# MIPI_FLAT_22PIN.net
KiCad netlist of a schematic drawn in Altium Designer
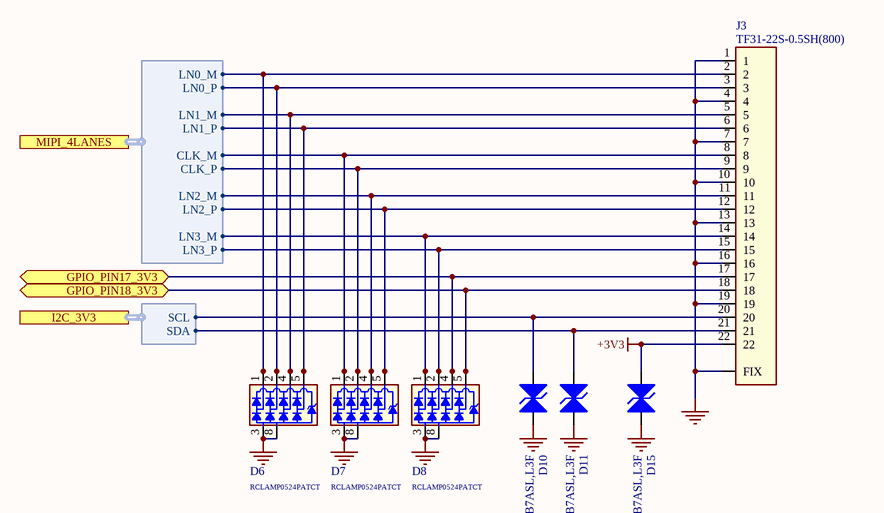
[diagram p0: MIPI_FLAT_22PIN.SchDoc]

(export (version "E")
  (design (tool "Eeschema 10.0.6"))
  (components
    (comp (ref "D6")
      (value "RCLAMP0524PATCT")
      (footprint "SLP2510P8")
      (description "TVS UNIDIRECTIONAL 4CH 0.8pF 5V SLP2510P8 10-pin 2.5x1.0x0.58mm")
      (fields (field (name "MANUFACTURER") "SEMTECH"))
      (libsource (lib "Clean") (part "RCLAMP0524PATCT"))
    )
    (comp (ref "D7")
      (value "RCLAMP0524PATCT")
      (footprint "SLP2510P8")
      (description "TVS UNIDIRECTIONAL 4CH 0.8pF 5V SLP2510P8 10-pin 2.5x1.0x0.58mm")
      (fields (field (name "MANUFACTURER") "SEMTECH"))
      (libsource (lib "Clean") (part "RCLAMP0524PATCT"))
    )
    (comp (ref "D8")
      (value "RCLAMP0524PATCT")
      (footprint "SLP2510P8")
      (description "TVS UNIDIRECTIONAL 4CH 0.8pF 5V SLP2510P8 10-pin 2.5x1.0x0.58mm")
      (fields (field (name "MANUFACTURER") "SEMTECH"))
      (libsource (lib "Clean") (part "RCLAMP0524PATCT"))
    )
    (comp (ref "D10")
      (value "DF2B7ASL,L3F")
      (footprint "DF2B7ASL,L3F")
      (description "TVS BIDIRECTIONAL SMD Vr 5.5V, Vbr min 5.8V, 0.62x0.32mm")
      (fields (field (name "MANUFACTURER") "TOSHIBA"))
      (libsource (lib "Clean") (part "Diode TVS"))
    )
    (comp (ref "D11")
      (value "DF2B7ASL,L3F")
      (footprint "DF2B7ASL,L3F")
      (description "TVS BIDIRECTIONAL SMD Vr 5.5V, Vbr min 5.8V, 0.62x0.32mm")
      (fields (field (name "MANUFACTURER") "TOSHIBA"))
      (libsource (lib "Clean") (part "Diode TVS"))
    )
    (comp (ref "D15")
      (value "DF2B7ASL,L3F")
      (footprint "DF2B7ASL,L3F")
      (description "TVS BIDIRECTIONAL SMD Vr 5.5V, Vbr min 5.8V, 0.62x0.32mm")
      (fields (field (name "MANUFACTURER") "TOSHIBA"))
      (libsource (lib "Clean") (part "Diode TVS"))
    )
    (comp (ref "J3")
      (value "TF31-22S-0.5SH(800)")
      (footprint "TF31-22S-0.5SH(800)")
      (description "CONN FFC/FPC Connector, 22 Contact(s), 1 Row(s), BOTTOM CONTACT, Female, Right Angle, 0.5mm Pitch")
      (fields (field (name "MANUFACTURER") "Hirose"))
      (libsource (lib "Clean") (part "TF31-22S-0.5SH(800)"))
    )
  )
  (nets
    (net (code "3") (name "+3V3") (class "Default")
      (node (ref "D15") (pin "2") (pinfunction "A2_2") (pintype "passive"))
      (node (ref "J3") (pin "22") (pinfunction "22_22") (pintype "passive"))
    )
    (net (code "4") (name "/GPIO_PIN17_3V3") (class "Default")
      (node (ref "D8") (pin "4") (pinfunction "4_4") (pintype "passive"))
      (node (ref "D8") (pin "7") (pinfunction "7_7") (pintype "passive"))
      (node (ref "J3") (pin "17") (pinfunction "17_17") (pintype "passive"))
    )
    (net (code "5") (name "/GPIO_PIN18_3V3") (class "Default")
      (node (ref "D8") (pin "5") (pinfunction "5_5") (pintype "passive"))
      (node (ref "D8") (pin "6") (pinfunction "6_6") (pintype "passive"))
      (node (ref "J3") (pin "18") (pinfunction "18_18") (pintype "passive"))
    )
    (net (code "8") (name "GND") (class "Default")
      (node (ref "D10") (pin "1") (pinfunction "A1_1") (pintype "passive"))
      (node (ref "D11") (pin "1") (pinfunction "A1_1") (pintype "passive"))
      (node (ref "D15") (pin "1") (pinfunction "A1_1") (pintype "passive"))
      (node (ref "D6") (pin "3") (pinfunction "3_3") (pintype "passive"))
      (node (ref "D6") (pin "8") (pinfunction "8_8") (pintype "passive"))
      (node (ref "D7") (pin "3") (pinfunction "3_3") (pintype "passive"))
      (node (ref "D7") (pin "8") (pinfunction "8_8") (pintype "passive"))
      (node (ref "D8") (pin "3") (pinfunction "3_3") (pintype "passive"))
      (node (ref "D8") (pin "8") (pinfunction "8_8") (pintype "passive"))
      (node (ref "J3") (pin "1") (pinfunction "1_1") (pintype "passive"))
      (node (ref "J3") (pin "10") (pinfunction "10_10") (pintype "passive"))
      (node (ref "J3") (pin "13") (pinfunction "13_13") (pintype "passive"))
      (node (ref "J3") (pin "16") (pinfunction "16_16") (pintype "passive"))
      (node (ref "J3") (pin "19") (pinfunction "19_19") (pintype "passive"))
      (node (ref "J3") (pin "4") (pinfunction "4_4") (pintype "passive"))
      (node (ref "J3") (pin "7") (pinfunction "7_7") (pintype "passive"))
      (node (ref "J3") (pin "FIX") (pinfunction "FIX_FIX") (pintype "passive"))
    )
    (net (code "9") (name "Net-(D6-Pad1)") (class "Default")
      (node (ref "D6") (pin "1") (pinfunction "1_1") (pintype "passive"))
      (node (ref "D6") (pin "10") (pinfunction "10_10") (pintype "passive"))
      (node (ref "J3") (pin "2") (pinfunction "2_2") (pintype "passive"))
    )
    (net (code "10") (name "Net-(D6-Pad2)") (class "Default")
      (node (ref "D6") (pin "2") (pinfunction "2_2") (pintype "passive"))
      (node (ref "D6") (pin "9") (pinfunction "9_9") (pintype "passive"))
      (node (ref "J3") (pin "3") (pinfunction "3_3") (pintype "passive"))
    )
    (net (code "11") (name "Net-(D6-Pad4)") (class "Default")
      (node (ref "D6") (pin "4") (pinfunction "4_4") (pintype "passive"))
      (node (ref "D6") (pin "7") (pinfunction "7_7") (pintype "passive"))
      (node (ref "J3") (pin "5") (pinfunction "5_5") (pintype "passive"))
    )
    (net (code "12") (name "Net-(D6-Pad5)") (class "Default")
      (node (ref "D6") (pin "5") (pinfunction "5_5") (pintype "passive"))
      (node (ref "D6") (pin "6") (pinfunction "6_6") (pintype "passive"))
      (node (ref "J3") (pin "6") (pinfunction "6_6") (pintype "passive"))
    )
    (net (code "13") (name "Net-(D7-Pad1)") (class "Default")
      (node (ref "D7") (pin "1") (pinfunction "1_1") (pintype "passive"))
      (node (ref "D7") (pin "10") (pinfunction "10_10") (pintype "passive"))
      (node (ref "J3") (pin "8") (pinfunction "8_8") (pintype "passive"))
    )
    (net (code "14") (name "Net-(D7-Pad2)") (class "Default")
      (node (ref "D7") (pin "2") (pinfunction "2_2") (pintype "passive"))
      (node (ref "D7") (pin "9") (pinfunction "9_9") (pintype "passive"))
      (node (ref "J3") (pin "9") (pinfunction "9_9") (pintype "passive"))
    )
    (net (code "15") (name "Net-(D7-Pad4)") (class "Default")
      (node (ref "D7") (pin "4") (pinfunction "4_4") (pintype "passive"))
      (node (ref "D7") (pin "7") (pinfunction "7_7") (pintype "passive"))
      (node (ref "J3") (pin "11") (pinfunction "11_11") (pintype "passive"))
    )
    (net (code "16") (name "Net-(D7-Pad5)") (class "Default")
      (node (ref "D7") (pin "5") (pinfunction "5_5") (pintype "passive"))
      (node (ref "D7") (pin "6") (pinfunction "6_6") (pintype "passive"))
      (node (ref "J3") (pin "12") (pinfunction "12_12") (pintype "passive"))
    )
    (net (code "17") (name "Net-(D8-Pad1)") (class "Default")
      (node (ref "D8") (pin "1") (pinfunction "1_1") (pintype "passive"))
      (node (ref "D8") (pin "10") (pinfunction "10_10") (pintype "passive"))
      (node (ref "J3") (pin "14") (pinfunction "14_14") (pintype "passive"))
    )
    (net (code "18") (name "Net-(D8-Pad2)") (class "Default")
      (node (ref "D8") (pin "2") (pinfunction "2_2") (pintype "passive"))
      (node (ref "D8") (pin "9") (pinfunction "9_9") (pintype "passive"))
      (node (ref "J3") (pin "15") (pinfunction "15_15") (pintype "passive"))
    )
    (net (code "19") (name "Net-(D10-A2)") (class "Default")
      (node (ref "D10") (pin "2") (pinfunction "A2_2") (pintype "passive"))
      (node (ref "J3") (pin "20") (pinfunction "20_20") (pintype "passive"))
    )
    (net (code "20") (name "Net-(D11-A2)") (class "Default")
      (node (ref "D11") (pin "2") (pinfunction "A2_2") (pintype "passive"))
      (node (ref "J3") (pin "21") (pinfunction "21_21") (pintype "passive"))
    )
  )
)
